# IRIS_Arduino_Shield_2.net
KiCad netlist of a schematic drawn in EAGLE
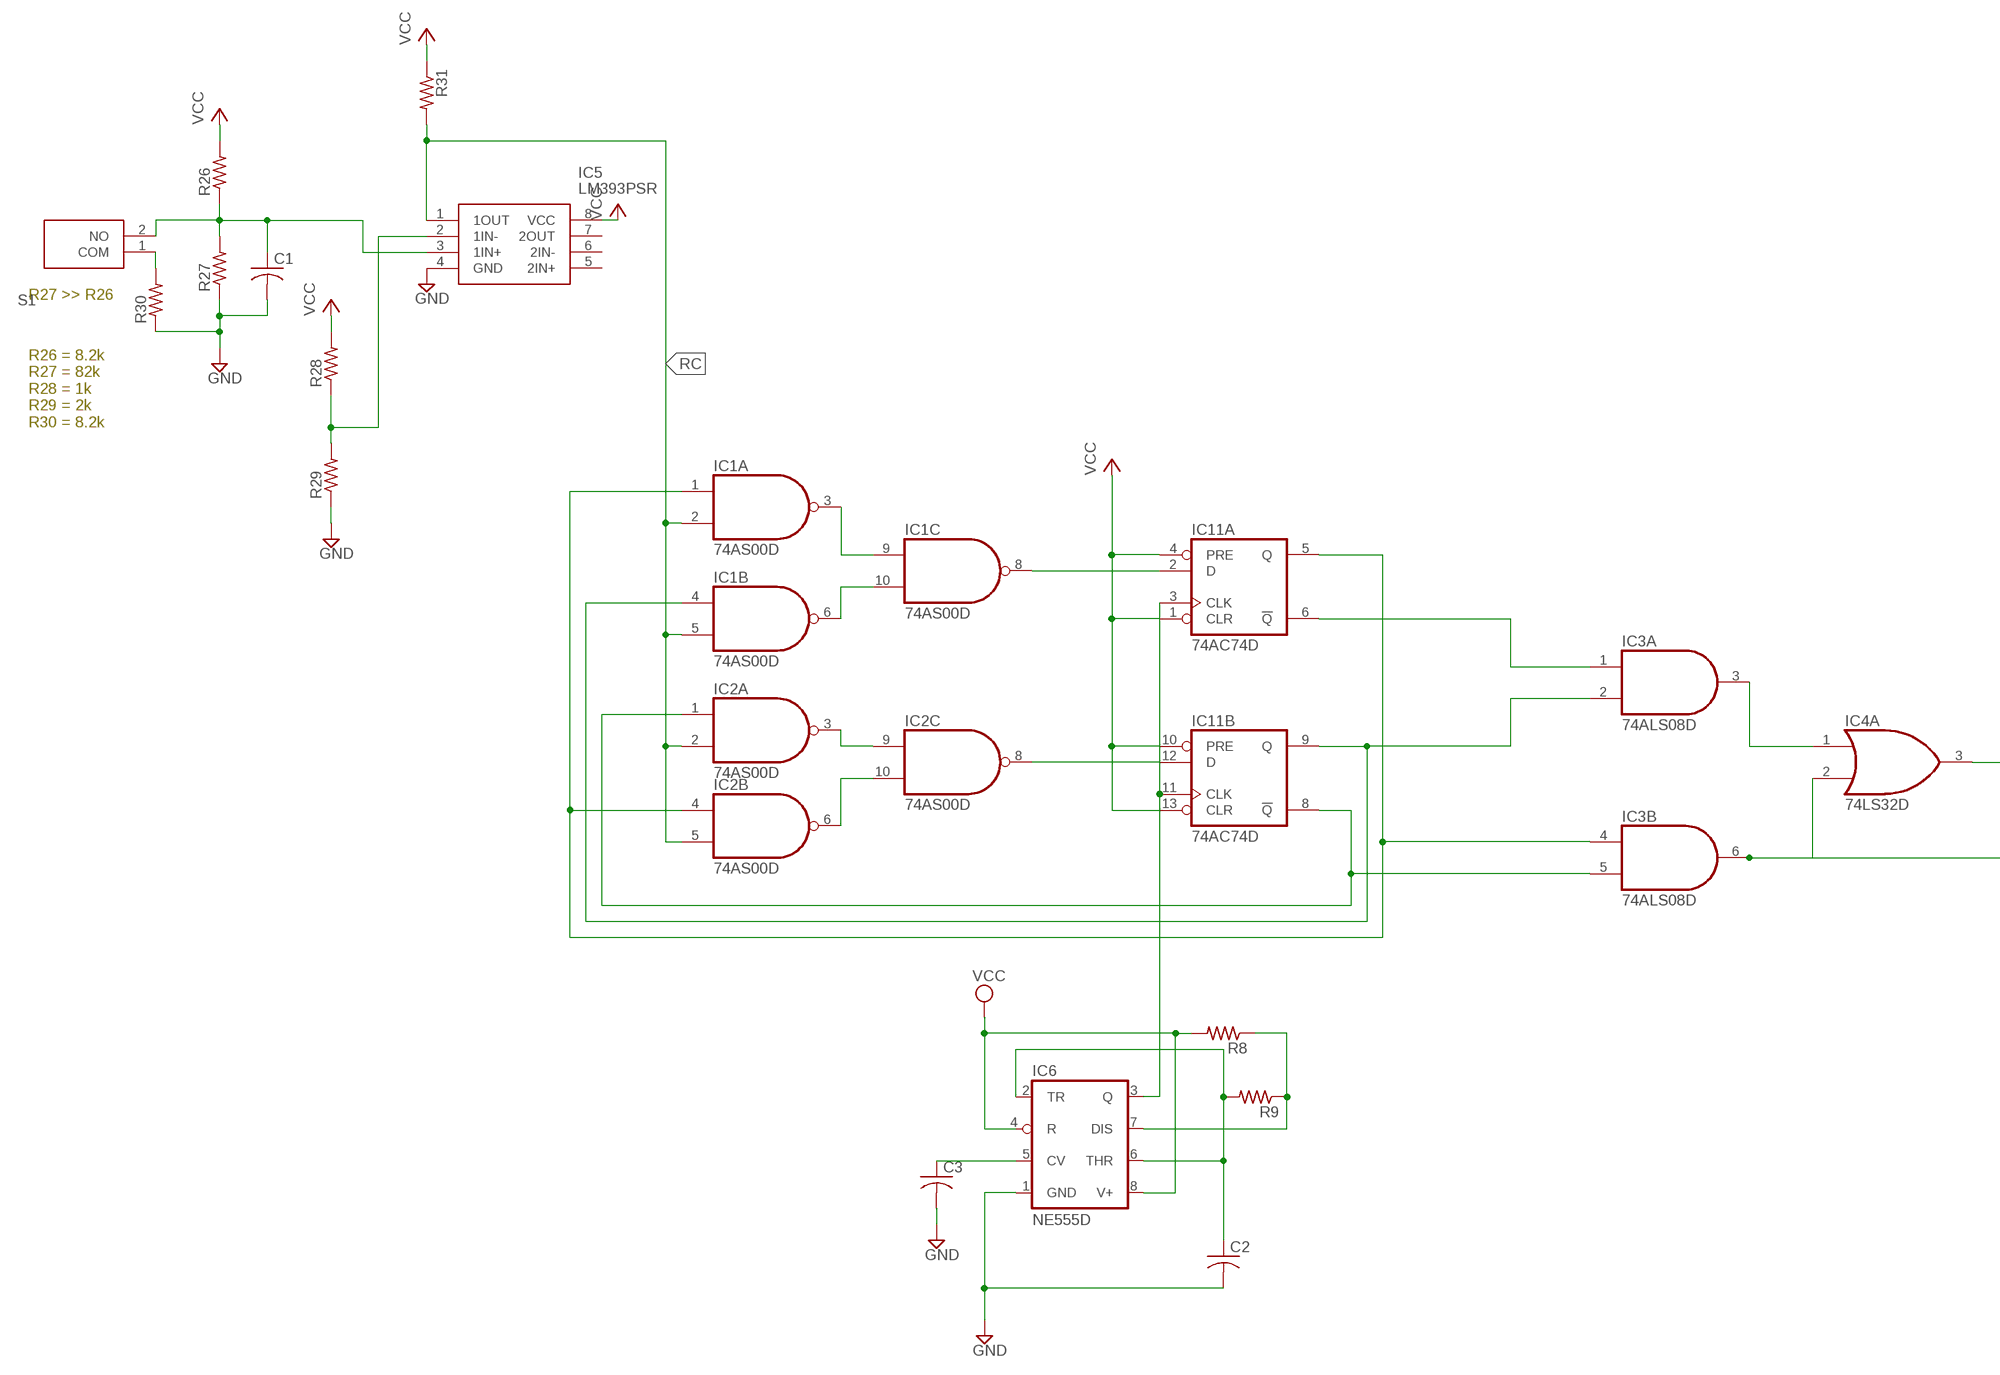
[diagram p0: schematic, sheet 1, part 1 of 2]
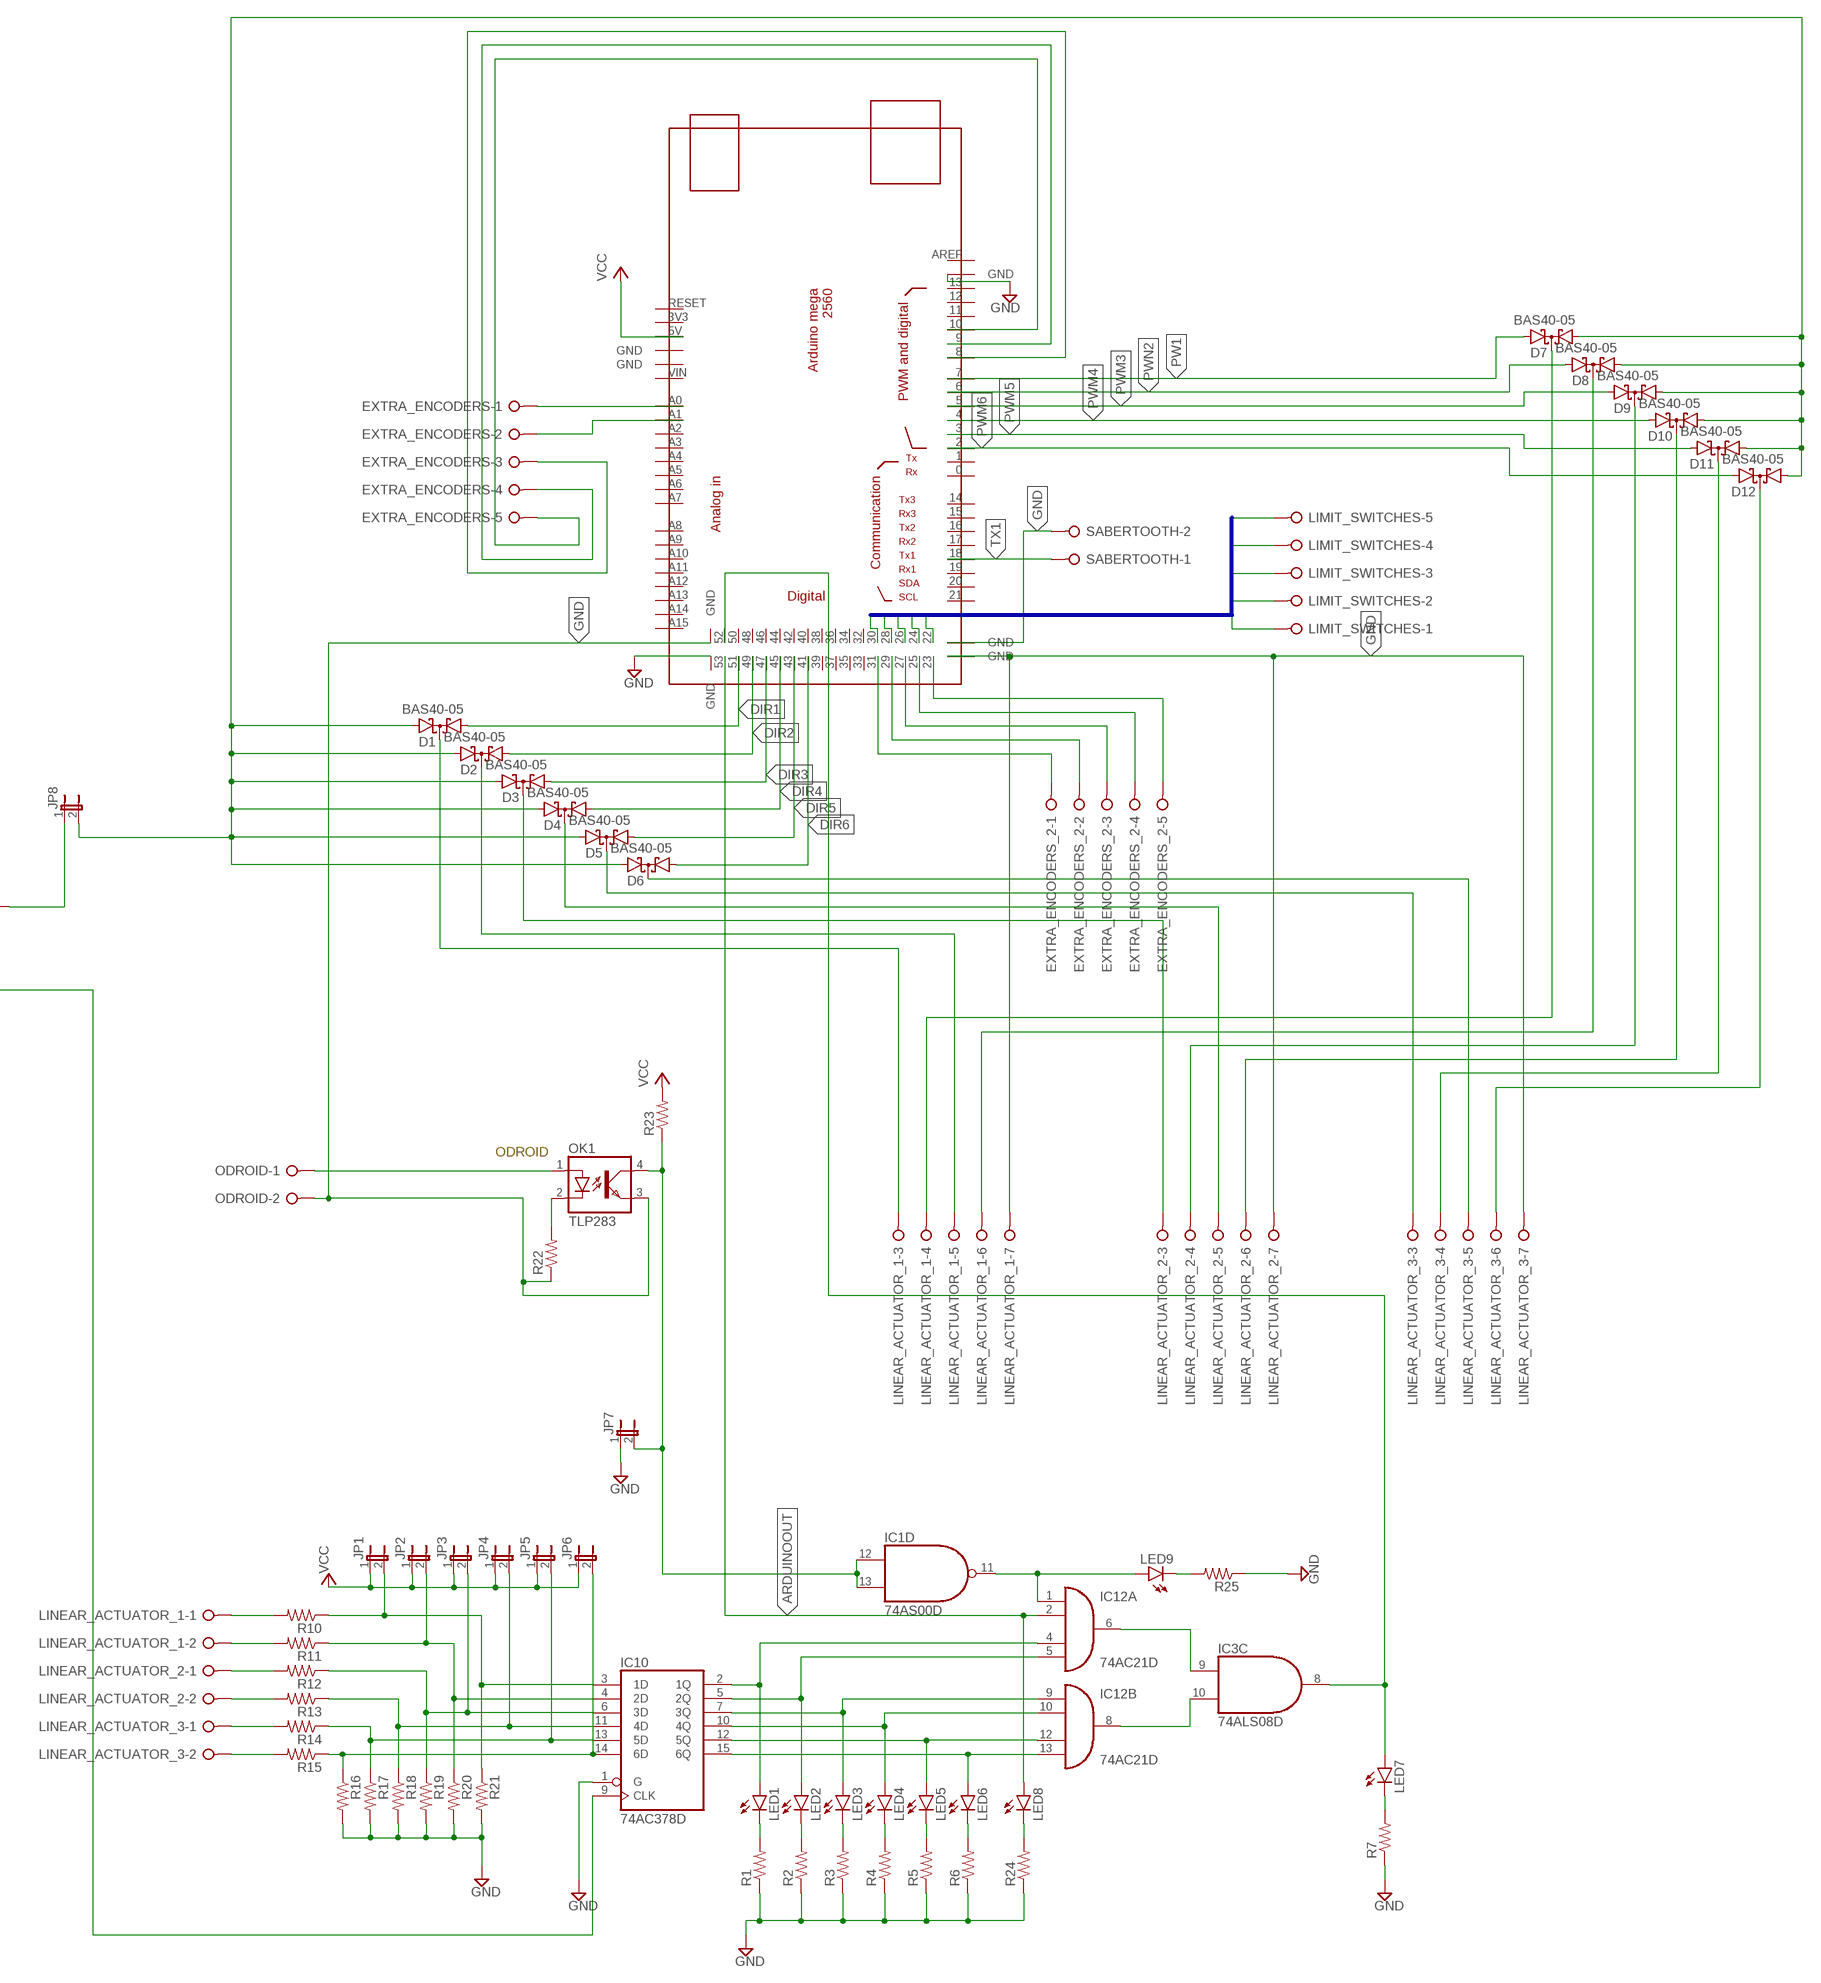
[diagram p1: schematic, sheet 1, part 2 of 2]

(export (version "E")
  (design (tool "Eeschema 10.0.6"))
  (components
    (comp (ref "C1")
      (value "C-USC0805")
      (footprint "eagle-import:C0805")
      (libsource (lib "eagle-import") (part "C-USC0805"))
    )
    (comp (ref "C2")
      (value "C-USC0805")
      (footprint "eagle-import:C0805")
      (libsource (lib "eagle-import") (part "C-USC0805"))
    )
    (comp (ref "C3")
      (value "C-USC0805")
      (footprint "eagle-import:C0805")
      (libsource (lib "eagle-import") (part "C-USC0805"))
    )
    (comp (ref "D1")
      (value "BAS40-05")
      (footprint "eagle-import:SOT23")
      (libsource (lib "eagle-import") (part "BAS40-05"))
    )
    (comp (ref "D2")
      (value "BAS40-05")
      (footprint "eagle-import:SOT23")
      (libsource (lib "eagle-import") (part "BAS40-05"))
    )
    (comp (ref "D3")
      (value "BAS40-05")
      (footprint "eagle-import:SOT23")
      (libsource (lib "eagle-import") (part "BAS40-05"))
    )
    (comp (ref "D4")
      (value "BAS40-05")
      (footprint "eagle-import:SOT23")
      (libsource (lib "eagle-import") (part "BAS40-05"))
    )
    (comp (ref "D5")
      (value "BAS40-05")
      (footprint "eagle-import:SOT23")
      (libsource (lib "eagle-import") (part "BAS40-05"))
    )
    (comp (ref "D6")
      (value "BAS40-05")
      (footprint "eagle-import:SOT23")
      (libsource (lib "eagle-import") (part "BAS40-05"))
    )
    (comp (ref "D7")
      (value "BAS40-05")
      (footprint "eagle-import:SOT23")
      (libsource (lib "eagle-import") (part "BAS40-05"))
    )
    (comp (ref "D8")
      (value "BAS40-05")
      (footprint "eagle-import:SOT23")
      (libsource (lib "eagle-import") (part "BAS40-05"))
    )
    (comp (ref "D9")
      (value "BAS40-05")
      (footprint "eagle-import:SOT23")
      (libsource (lib "eagle-import") (part "BAS40-05"))
    )
    (comp (ref "D10")
      (value "BAS40-05")
      (footprint "eagle-import:SOT23")
      (libsource (lib "eagle-import") (part "BAS40-05"))
    )
    (comp (ref "D11")
      (value "BAS40-05")
      (footprint "eagle-import:SOT23")
      (libsource (lib "eagle-import") (part "BAS40-05"))
    )
    (comp (ref "D12")
      (value "BAS40-05")
      (footprint "eagle-import:SOT23")
      (libsource (lib "eagle-import") (part "BAS40-05"))
    )
    (comp (ref "EXTRA_ENCODERS")
      (value "W237-05P")
      (footprint "eagle-import:W237-5P")
      (libsource (lib "eagle-import") (part "W237-05P"))
    )
    (comp (ref "EXTRA_ENCODERS_2")
      (value "W237-05P")
      (footprint "eagle-import:W237-5P")
      (libsource (lib "eagle-import") (part "W237-05P"))
    )
    (comp (ref "IC1")
      (value "74AS00D")
      (footprint "eagle-import:SO14")
      (libsource (lib "eagle-import") (part "7400DAS"))
    )
    (comp (ref "IC2")
      (value "74AS00D")
      (footprint "eagle-import:SO14")
      (libsource (lib "eagle-import") (part "7400DAS"))
    )
    (comp (ref "IC3")
      (value "74ALS08D")
      (footprint "eagle-import:SO14")
      (libsource (lib "eagle-import") (part "7408DALS"))
    )
    (comp (ref "IC4")
      (value "74LS32D")
      (footprint "eagle-import:SO14")
      (libsource (lib "eagle-import") (part "7432DLS"))
    )
    (comp (ref "IC5")
      (value "LM393PSR")
      (footprint "eagle-import:SOIC127P780X200-8N")
      (fields (field (name "MOUSER_PART_NUMBER") "595-LM393PSR"))
      (libsource (lib "eagle-import") (part "LM393PSR"))
    )
    (comp (ref "IC6")
      (value "NE555D")
      (footprint "eagle-import:SO08")
      (libsource (lib "eagle-import") (part "555DNE"))
    )
    (comp (ref "IC10")
      (value "74AC378D")
      (footprint "eagle-import:SO16")
      (libsource (lib "eagle-import") (part "74378DAC"))
    )
    (comp (ref "IC11")
      (value "74AC74D")
      (footprint "eagle-import:SO14")
      (libsource (lib "eagle-import") (part "7474DAC"))
    )
    (comp (ref "IC12")
      (value "74AC21D")
      (footprint "eagle-import:SO14")
      (libsource (lib "eagle-import") (part "7421DAC"))
    )
    (comp (ref "JP1")
      (value "JP1E")
      (footprint "eagle-import:JP1")
      (libsource (lib "eagle-import") (part "JP1E"))
    )
    (comp (ref "JP2")
      (value "JP1E")
      (footprint "eagle-import:JP1")
      (libsource (lib "eagle-import") (part "JP1E"))
    )
    (comp (ref "JP3")
      (value "JP1E")
      (footprint "eagle-import:JP1")
      (libsource (lib "eagle-import") (part "JP1E"))
    )
    (comp (ref "JP4")
      (value "JP1E")
      (footprint "eagle-import:JP1")
      (libsource (lib "eagle-import") (part "JP1E"))
    )
    (comp (ref "JP5")
      (value "JP1E")
      (footprint "eagle-import:JP1")
      (libsource (lib "eagle-import") (part "JP1E"))
    )
    (comp (ref "JP6")
      (value "JP1E")
      (footprint "eagle-import:JP1")
      (libsource (lib "eagle-import") (part "JP1E"))
    )
    (comp (ref "JP7")
      (value "JP1E")
      (footprint "eagle-import:JP1")
      (libsource (lib "eagle-import") (part "JP1E"))
    )
    (comp (ref "JP8")
      (value "JP1E")
      (footprint "eagle-import:JP1")
      (libsource (lib "eagle-import") (part "JP1E"))
    )
    (comp (ref "LED1")
      (value "LEDCHIPLED_1206")
      (footprint "eagle-import:CHIPLED_1206")
      (libsource (lib "eagle-import") (part "LEDCHIPLED_1206"))
    )
    (comp (ref "LED2")
      (value "LEDCHIPLED_1206")
      (footprint "eagle-import:CHIPLED_1206")
      (libsource (lib "eagle-import") (part "LEDCHIPLED_1206"))
    )
    (comp (ref "LED3")
      (value "LEDCHIPLED_1206")
      (footprint "eagle-import:CHIPLED_1206")
      (libsource (lib "eagle-import") (part "LEDCHIPLED_1206"))
    )
    (comp (ref "LED4")
      (value "LEDCHIPLED_1206")
      (footprint "eagle-import:CHIPLED_1206")
      (libsource (lib "eagle-import") (part "LEDCHIPLED_1206"))
    )
    (comp (ref "LED5")
      (value "LEDCHIPLED_1206")
      (footprint "eagle-import:CHIPLED_1206")
      (libsource (lib "eagle-import") (part "LEDCHIPLED_1206"))
    )
    (comp (ref "LED6")
      (value "LEDCHIPLED_1206")
      (footprint "eagle-import:CHIPLED_1206")
      (libsource (lib "eagle-import") (part "LEDCHIPLED_1206"))
    )
    (comp (ref "LED7")
      (value "LEDCHIPLED_1206")
      (footprint "eagle-import:CHIPLED_1206")
      (libsource (lib "eagle-import") (part "LEDCHIPLED_1206"))
    )
    (comp (ref "LED8")
      (value "LEDCHIPLED_1206")
      (footprint "eagle-import:CHIPLED_1206")
      (libsource (lib "eagle-import") (part "LEDCHIPLED_1206"))
    )
    (comp (ref "LED9")
      (value "LEDCHIPLED_1206")
      (footprint "eagle-import:CHIPLED_1206")
      (libsource (lib "eagle-import") (part "LEDCHIPLED_1206"))
    )
    (comp (ref "LIMIT_SWITCHES")
      (value "W237-05P")
      (footprint "eagle-import:W237-5P")
      (libsource (lib "eagle-import") (part "W237-05P"))
    )
    (comp (ref "LINEAR_ACTUATOR_1")
      (value "W237-07P")
      (footprint "eagle-import:W237-7P")
      (libsource (lib "eagle-import") (part "W237-07P"))
    )
    (comp (ref "LINEAR_ACTUATOR_2")
      (value "W237-07P")
      (footprint "eagle-import:W237-7P")
      (libsource (lib "eagle-import") (part "W237-07P"))
    )
    (comp (ref "LINEAR_ACTUATOR_3")
      (value "W237-07P")
      (footprint "eagle-import:W237-7P")
      (libsource (lib "eagle-import") (part "W237-07P"))
    )
    (comp (ref "ODROID")
      (value "W237-02P")
      (footprint "eagle-import:W237-132")
      (libsource (lib "eagle-import") (part "W237-02P"))
    )
    (comp (ref "OK1")
      (value "TLP283")
      (footprint "eagle-import:MINI-FLAT-4")
      (libsource (lib "eagle-import") (part "TLP283"))
    )
    (comp (ref "R1")
      (value "R-US_R0805")
      (footprint "eagle-import:R0805")
      (libsource (lib "eagle-import") (part "R-US_R0805"))
    )
    (comp (ref "R2")
      (value "R-US_R0805")
      (footprint "eagle-import:R0805")
      (libsource (lib "eagle-import") (part "R-US_R0805"))
    )
    (comp (ref "R3")
      (value "R-US_R0805")
      (footprint "eagle-import:R0805")
      (libsource (lib "eagle-import") (part "R-US_R0805"))
    )
    (comp (ref "R4")
      (value "R-US_R0805")
      (footprint "eagle-import:R0805")
      (libsource (lib "eagle-import") (part "R-US_R0805"))
    )
    (comp (ref "R5")
      (value "R-US_R0805")
      (footprint "eagle-import:R0805")
      (libsource (lib "eagle-import") (part "R-US_R0805"))
    )
    (comp (ref "R6")
      (value "R-US_R0805")
      (footprint "eagle-import:R0805")
      (libsource (lib "eagle-import") (part "R-US_R0805"))
    )
    (comp (ref "R7")
      (value "R-US_R0805")
      (footprint "eagle-import:R0805")
      (libsource (lib "eagle-import") (part "R-US_R0805"))
    )
    (comp (ref "R8")
      (value "R-US_R0805")
      (footprint "eagle-import:R0805")
      (libsource (lib "eagle-import") (part "R-US_R0805"))
    )
    (comp (ref "R9")
      (value "R-US_R0805")
      (footprint "eagle-import:R0805")
      (libsource (lib "eagle-import") (part "R-US_R0805"))
    )
    (comp (ref "R10")
      (value "R-US_R0805")
      (footprint "eagle-import:R0805")
      (libsource (lib "eagle-import") (part "R-US_R0805"))
    )
    (comp (ref "R11")
      (value "R-US_R0805")
      (footprint "eagle-import:R0805")
      (libsource (lib "eagle-import") (part "R-US_R0805"))
    )
    (comp (ref "R12")
      (value "R-US_R0805")
      (footprint "eagle-import:R0805")
      (libsource (lib "eagle-import") (part "R-US_R0805"))
    )
    (comp (ref "R13")
      (value "R-US_R0805")
      (footprint "eagle-import:R0805")
      (libsource (lib "eagle-import") (part "R-US_R0805"))
    )
    (comp (ref "R14")
      (value "R-US_R0805")
      (footprint "eagle-import:R0805")
      (libsource (lib "eagle-import") (part "R-US_R0805"))
    )
    (comp (ref "R15")
      (value "R-US_R0805")
      (footprint "eagle-import:R0805")
      (libsource (lib "eagle-import") (part "R-US_R0805"))
    )
    (comp (ref "R16")
      (value "R-US_R0805")
      (footprint "eagle-import:R0805")
      (libsource (lib "eagle-import") (part "R-US_R0805"))
    )
    (comp (ref "R17")
      (value "R-US_R0805")
      (footprint "eagle-import:R0805")
      (libsource (lib "eagle-import") (part "R-US_R0805"))
    )
    (comp (ref "R18")
      (value "R-US_R0805")
      (footprint "eagle-import:R0805")
      (libsource (lib "eagle-import") (part "R-US_R0805"))
    )
    (comp (ref "R19")
      (value "R-US_R0805")
      (footprint "eagle-import:R0805")
      (libsource (lib "eagle-import") (part "R-US_R0805"))
    )
    (comp (ref "R20")
      (value "R-US_R0805")
      (footprint "eagle-import:R0805")
      (libsource (lib "eagle-import") (part "R-US_R0805"))
    )
    (comp (ref "R21")
      (value "R-US_R0805")
      (footprint "eagle-import:R0805")
      (libsource (lib "eagle-import") (part "R-US_R0805"))
    )
    (comp (ref "R22")
      (value "R-US_R0805")
      (footprint "eagle-import:R0805")
      (libsource (lib "eagle-import") (part "R-US_R0805"))
    )
    (comp (ref "R23")
      (value "R-US_R0805")
      (footprint "eagle-import:R0805")
      (libsource (lib "eagle-import") (part "R-US_R0805"))
    )
    (comp (ref "R24")
      (value "R-US_R0805")
      (footprint "eagle-import:R0805")
      (libsource (lib "eagle-import") (part "R-US_R0805"))
    )
    (comp (ref "R25")
      (value "R-US_R0805")
      (footprint "eagle-import:R0805")
      (libsource (lib "eagle-import") (part "R-US_R0805"))
    )
    (comp (ref "R26")
      (value "R-US_R0805")
      (footprint "eagle-import:R0805")
      (libsource (lib "eagle-import") (part "R-US_R0805"))
    )
    (comp (ref "R27")
      (value "R-US_R0805")
      (footprint "eagle-import:R0805")
      (libsource (lib "eagle-import") (part "R-US_R0805"))
    )
    (comp (ref "R28")
      (value "R-US_R0805")
      (footprint "eagle-import:R0805")
      (libsource (lib "eagle-import") (part "R-US_R0805"))
    )
    (comp (ref "R29")
      (value "R-US_R0805")
      (footprint "eagle-import:R0805")
      (libsource (lib "eagle-import") (part "R-US_R0805"))
    )
    (comp (ref "R30")
      (value "R-US_R0805")
      (footprint "eagle-import:R0805")
      (libsource (lib "eagle-import") (part "R-US_R0805"))
    )
    (comp (ref "R31")
      (value "R-US_R0805")
      (footprint "eagle-import:R0805")
      (libsource (lib "eagle-import") (part "R-US_R0805"))
    )
    (comp (ref "S1")
      (value "PTS636_SL43_SMTR_LFS")
      (footprint "eagle-import:PTS636SL43SMTRLFS")
      (fields
        (field (name "MANUFACTURER_PART_NUMBER") "PTS636 SL43 SMTR LFS")
        (field (name "MOUSER_PART_NUMBER") "611-PTS636SL43SMTRLF")
      )
      (libsource (lib "eagle-import") (part "PTS636_SL43_SMTR_LFS"))
    )
    (comp (ref "SABERTOOTH")
      (value "W237-02P")
      (footprint "eagle-import:W237-132")
      (libsource (lib "eagle-import") (part "W237-02P"))
    )
    (comp (ref "U$1")
      (value "MEGA_DEVICE")
      (footprint "eagle-import:MEGAOUTLINE")
      (libsource (lib "eagle-import") (part "MEGA_DEVICE"))
    )
  )
  (nets
    (net (code "1") (name "/N$77") (class "Default")
      (node (ref "LIMIT_SWITCHES") (pin "1") (pinfunction "KL_1") (pintype "passive"))
      (node (ref "U$1") (pin "30") (pinfunction "30_30") (pintype "bidirectional"))
    )
    (net (code "2") (name "/N$78") (class "Default")
      (node (ref "LIMIT_SWITCHES") (pin "2") (pinfunction "KL_2") (pintype "passive"))
      (node (ref "U$1") (pin "28") (pinfunction "28_28") (pintype "bidirectional"))
    )
    (net (code "3") (name "/N$79") (class "Default")
      (node (ref "LIMIT_SWITCHES") (pin "3") (pinfunction "KL_3") (pintype "passive"))
      (node (ref "U$1") (pin "26") (pinfunction "26_26") (pintype "bidirectional"))
    )
    (net (code "4") (name "/N$80") (class "Default")
      (node (ref "LIMIT_SWITCHES") (pin "4") (pinfunction "KL_4") (pintype "passive"))
      (node (ref "U$1") (pin "24") (pinfunction "24_24") (pintype "bidirectional"))
    )
    (net (code "5") (name "/N$81") (class "Default")
      (node (ref "LIMIT_SWITCHES") (pin "5") (pinfunction "KL_5") (pintype "passive"))
      (node (ref "U$1") (pin "22") (pinfunction "22_22") (pintype "bidirectional"))
    )
    (net (code "6") (name "ARDUINOOUT") (class "Default")
      (node (ref "IC12") (pin "2") (pinfunction "I1_2") (pintype "input"))
      (node (ref "LED8") (pin "A") (pinfunction "A_A") (pintype "passive"))
      (node (ref "U$1") (pin "53") (pinfunction "53_53") (pintype "bidirectional"))
    )
    (net (code "7") (name "DIR1") (class "Default")
      (node (ref "D1") (pin "1") (pinfunction "A1_1") (pintype "passive"))
      (node (ref "U$1") (pin "51") (pinfunction "51_51") (pintype "bidirectional"))
    )
    (net (code "8") (name "DIR2") (class "Default")
      (node (ref "D2") (pin "1") (pinfunction "A1_1") (pintype "passive"))
      (node (ref "U$1") (pin "49") (pinfunction "49_49") (pintype "bidirectional"))
    )
    (net (code "9") (name "DIR3") (class "Default")
      (node (ref "D3") (pin "1") (pinfunction "A1_1") (pintype "passive"))
      (node (ref "U$1") (pin "47") (pinfunction "47_47") (pintype "bidirectional"))
    )
    (net (code "10") (name "DIR4") (class "Default")
      (node (ref "D4") (pin "1") (pinfunction "A1_1") (pintype "passive"))
      (node (ref "U$1") (pin "45") (pinfunction "45_45") (pintype "bidirectional"))
    )
    (net (code "11") (name "DIR5") (class "Default")
      (node (ref "D5") (pin "1") (pinfunction "A1_1") (pintype "passive"))
      (node (ref "U$1") (pin "43") (pinfunction "43_43") (pintype "bidirectional"))
    )
    (net (code "12") (name "DIR6") (class "Default")
      (node (ref "D6") (pin "1") (pinfunction "A1_1") (pintype "passive"))
      (node (ref "U$1") (pin "41") (pinfunction "41_41") (pintype "bidirectional"))
    )
    (net (code "13") (name "GND") (class "Default")
      (node (ref "C1") (pin "2") (pinfunction "2_2") (pintype "passive"))
      (node (ref "C2") (pin "2") (pinfunction "2_2") (pintype "passive"))
      (node (ref "C3") (pin "2") (pinfunction "2_2") (pintype "passive"))
      (node (ref "IC10") (pin "1") (pinfunction "G_1") (pintype "input"))
      (node (ref "IC5") (pin "4") (pinfunction "GND_4") (pintype "bidirectional"))
      (node (ref "IC6") (pin "1") (pinfunction "GND_1") (pintype "power_in"))
      (node (ref "JP7") (pin "1") (pinfunction "1_1") (pintype "passive"))
      (node (ref "LINEAR_ACTUATOR_1") (pin "7") (pinfunction "KL_7") (pintype "passive"))
      (node (ref "LINEAR_ACTUATOR_2") (pin "7") (pinfunction "KL_7") (pintype "passive"))
      (node (ref "LINEAR_ACTUATOR_3") (pin "7") (pinfunction "KL_7") (pintype "passive"))
      (node (ref "ODROID") (pin "2") (pinfunction "KL_2") (pintype "passive"))
      (node (ref "OK1") (pin "3") (pinfunction "EMIT_3") (pintype "passive"))
      (node (ref "R1") (pin "1") (pinfunction "1_1") (pintype "passive"))
      (node (ref "R16") (pin "2") (pinfunction "2_2") (pintype "passive"))
      (node (ref "R17") (pin "2") (pinfunction "2_2") (pintype "passive"))
      (node (ref "R18") (pin "2") (pinfunction "2_2") (pintype "passive"))
      (node (ref "R19") (pin "2") (pinfunction "2_2") (pintype "passive"))
      (node (ref "R2") (pin "1") (pinfunction "1_1") (pintype "passive"))
      (node (ref "R20") (pin "2") (pinfunction "2_2") (pintype "passive"))
      (node (ref "R21") (pin "2") (pinfunction "2_2") (pintype "passive"))
      (node (ref "R22") (pin "1") (pinfunction "1_1") (pintype "passive"))
      (node (ref "R24") (pin "1") (pinfunction "1_1") (pintype "passive"))
      (node (ref "R25") (pin "1") (pinfunction "1_1") (pintype "passive"))
      (node (ref "R27") (pin "1") (pinfunction "1_1") (pintype "passive"))
      (node (ref "R29") (pin "1") (pinfunction "1_1") (pintype "passive"))
      (node (ref "R3") (pin "1") (pinfunction "1_1") (pintype "passive"))
      (node (ref "R30") (pin "1") (pinfunction "1_1") (pintype "passive"))
      (node (ref "R4") (pin "1") (pinfunction "1_1") (pintype "passive"))
      (node (ref "R5") (pin "1") (pinfunction "1_1") (pintype "passive"))
      (node (ref "R6") (pin "1") (pinfunction "1_1") (pintype "passive"))
      (node (ref "R7") (pin "1") (pinfunction "1_1") (pintype "passive"))
      (node (ref "SABERTOOTH") (pin "2") (pinfunction "KL_2") (pintype "passive"))
      (node (ref "U$1") (pin "GND@1") (pinfunction "GND_GND@1") (pintype "bidirectional"))
      (node (ref "U$1") (pin "GND@4") (pinfunction "GND_GND@4") (pintype "bidirectional"))
      (node (ref "U$1") (pin "GND@5") (pinfunction "GND_GND@5") (pintype "bidirectional"))
      (node (ref "U$1") (pin "GND@6") (pinfunction "GND_GND@6") (pintype "bidirectional"))
      (node (ref "U$1") (pin "GND@7") (pinfunction "GND_GND@7") (pintype "bidirectional"))
    )
    (net (code "14") (name "Net-(D1-A2)") (class "Default")
      (node (ref "D1") (pin "2") (pinfunction "A2_2") (pintype "passive"))
      (node (ref "D10") (pin "1") (pinfunction "A1_1") (pintype "passive"))
      (node (ref "D11") (pin "1") (pinfunction "A1_1") (pintype "passive"))
      (node (ref "D12") (pin "1") (pinfunction "A1_1") (pintype "passive"))
      (node (ref "D2") (pin "2") (pinfunction "A2_2") (pintype "passive"))
      (node (ref "D3") (pin "2") (pinfunction "A2_2") (pintype "passive"))
      (node (ref "D4") (pin "2") (pinfunction "A2_2") (pintype "passive"))
      (node (ref "D5") (pin "2") (pinfunction "A2_2") (pintype "passive"))
      (node (ref "D6") (pin "2") (pinfunction "A2_2") (pintype "passive"))
      (node (ref "D7") (pin "1") (pinfunction "A1_1") (pintype "passive"))
      (node (ref "D8") (pin "1") (pinfunction "A1_1") (pintype "passive"))
      (node (ref "D9") (pin "1") (pinfunction "A1_1") (pintype "passive"))
      (node (ref "JP8") (pin "2") (pinfunction "2_2") (pintype "passive"))
    )
    (net (code "15") (name "Net-(D1-C)") (class "Default")
      (node (ref "D1") (pin "3") (pinfunction "C_3") (pintype "passive"))
      (node (ref "LINEAR_ACTUATOR_1") (pin "3") (pinfunction "KL_3") (pintype "passive"))
    )
    (net (code "16") (name "Net-(D2-C)") (class "Default")
      (node (ref "D2") (pin "3") (pinfunction "C_3") (pintype "passive"))
      (node (ref "LINEAR_ACTUATOR_1") (pin "5") (pinfunction "KL_5") (pintype "passive"))
    )
    (net (code "17") (name "Net-(D3-C)") (class "Default")
      (node (ref "D3") (pin "3") (pinfunction "C_3") (pintype "passive"))
      (node (ref "LINEAR_ACTUATOR_2") (pin "3") (pinfunction "KL_3") (pintype "passive"))
    )
    (net (code "18") (name "Net-(D4-C)") (class "Default")
      (node (ref "D4") (pin "3") (pinfunction "C_3") (pintype "passive"))
      (node (ref "LINEAR_ACTUATOR_2") (pin "5") (pinfunction "KL_5") (pintype "passive"))
    )
    (net (code "19") (name "Net-(D5-C)") (class "Default")
      (node (ref "D5") (pin "3") (pinfunction "C_3") (pintype "passive"))
      (node (ref "LINEAR_ACTUATOR_3") (pin "3") (pinfunction "KL_3") (pintype "passive"))
    )
    (net (code "20") (name "Net-(D6-C)") (class "Default")
      (node (ref "D6") (pin "3") (pinfunction "C_3") (pintype "passive"))
      (node (ref "LINEAR_ACTUATOR_3") (pin "5") (pinfunction "KL_5") (pintype "passive"))
    )
    (net (code "21") (name "Net-(D7-C)") (class "Default")
      (node (ref "D7") (pin "3") (pinfunction "C_3") (pintype "passive"))
      (node (ref "LINEAR_ACTUATOR_1") (pin "4") (pinfunction "KL_4") (pintype "passive"))
    )
    (net (code "22") (name "Net-(D8-C)") (class "Default")
      (node (ref "D8") (pin "3") (pinfunction "C_3") (pintype "passive"))
      (node (ref "LINEAR_ACTUATOR_1") (pin "6") (pinfunction "KL_6") (pintype "passive"))
    )
    (net (code "23") (name "Net-(D9-C)") (class "Default")
      (node (ref "D9") (pin "3") (pinfunction "C_3") (pintype "passive"))
      (node (ref "LINEAR_ACTUATOR_2") (pin "4") (pinfunction "KL_4") (pintype "passive"))
    )
    (net (code "24") (name "Net-(D10-C)") (class "Default")
      (node (ref "D10") (pin "3") (pinfunction "C_3") (pintype "passive"))
      (node (ref "LINEAR_ACTUATOR_2") (pin "6") (pinfunction "KL_6") (pintype "passive"))
    )
    (net (code "25") (name "Net-(D11-C)") (class "Default")
      (node (ref "D11") (pin "3") (pinfunction "C_3") (pintype "passive"))
      (node (ref "LINEAR_ACTUATOR_3") (pin "4") (pinfunction "KL_4") (pintype "passive"))
    )
    (net (code "26") (name "Net-(D12-C)") (class "Default")
      (node (ref "D12") (pin "3") (pinfunction "C_3") (pintype "passive"))
      (node (ref "LINEAR_ACTUATOR_3") (pin "6") (pinfunction "KL_6") (pintype "passive"))
    )
    (net (code "27") (name "Net-(EXTRA_ENCODERSA-KL)") (class "Default")
      (node (ref "EXTRA_ENCODERS") (pin "1") (pinfunction "KL_1") (pintype "passive"))
      (node (ref "U$1") (pin "A0") (pinfunction "A0_A0") (pintype "bidirectional"))
    )
    (net (code "28") (name "Net-(EXTRA_ENCODERSB-KL)") (class "Default")
      (node (ref "EXTRA_ENCODERS") (pin "2") (pinfunction "KL_2") (pintype "passive"))
      (node (ref "U$1") (pin "A1") (pinfunction "A1_A1") (pintype "bidirectional"))
    )
    (net (code "29") (name "Net-(EXTRA_ENCODERSC-KL)") (class "Default")
      (node (ref "EXTRA_ENCODERS") (pin "3") (pinfunction "KL_3") (pintype "passive"))
      (node (ref "U$1") (pin "8") (pinfunction "8_8") (pintype "bidirectional"))
    )
    (net (code "30") (name "Net-(EXTRA_ENCODERSD-KL)") (class "Default")
      (node (ref "EXTRA_ENCODERS") (pin "4") (pinfunction "KL_4") (pintype "passive"))
      (node (ref "U$1") (pin "9") (pinfunction "9_9") (pintype "bidirectional"))
    )
    (net (code "31") (name "Net-(EXTRA_ENCODERSE-KL)") (class "Default")
      (node (ref "EXTRA_ENCODERS") (pin "5") (pinfunction "KL_5") (pintype "passive"))
      (node (ref "U$1") (pin "10") (pinfunction "10_10") (pintype "bidirectional"))
    )
    (net (code "32") (name "Net-(EXTRA_ENCODERS_2A-KL)") (class "Default")
      (node (ref "EXTRA_ENCODERS_2") (pin "1") (pinfunction "KL_1") (pintype "passive"))
      (node (ref "U$1") (pin "31") (pinfunction "31_31") (pintype "bidirectional"))
    )
    (net (code "33") (name "Net-(EXTRA_ENCODERS_2B-KL)") (class "Default")
      (node (ref "EXTRA_ENCODERS_2") (pin "2") (pinfunction "KL_2") (pintype "passive"))
      (node (ref "U$1") (pin "29") (pinfunction "29_29") (pintype "bidirectional"))
    )
    (net (code "34") (name "Net-(EXTRA_ENCODERS_2C-KL)") (class "Default")
      (node (ref "EXTRA_ENCODERS_2") (pin "3") (pinfunction "KL_3") (pintype "passive"))
      (node (ref "U$1") (pin "27") (pinfunction "27_27") (pintype "bidirectional"))
    )
    (net (code "35") (name "Net-(EXTRA_ENCODERS_2D-KL)") (class "Default")
      (node (ref "EXTRA_ENCODERS_2") (pin "4") (pinfunction "KL_4") (pintype "passive"))
      (node (ref "U$1") (pin "25") (pinfunction "25_25") (pintype "bidirectional"))
    )
    (net (code "36") (name "Net-(EXTRA_ENCODERS_2E-KL)") (class "Default")
      (node (ref "EXTRA_ENCODERS_2") (pin "5") (pinfunction "KL_5") (pintype "passive"))
      (node (ref "U$1") (pin "23") (pinfunction "23_23") (pintype "bidirectional"))
    )
    (net (code "37") (name "Net-(IC1A-O)") (class "Default")
      (node (ref "IC1") (pin "3") (pinfunction "O_3") (pintype "output"))
      (node (ref "IC1") (pin "9") (pinfunction "I0_9") (pintype "input"))
    )
    (net (code "38") (name "Net-(IC1B-O)") (class "Default")
      (node (ref "IC1") (pin "10") (pinfunction "I1_10") (pintype "input"))
      (node (ref "IC1") (pin "6") (pinfunction "O_6") (pintype "output"))
    )
    (net (code "39") (name "Net-(IC1D-I0)") (class "Default")
      (node (ref "IC1") (pin "12") (pinfunction "I0_12") (pintype "input"))
      (node (ref "IC1") (pin "13") (pinfunction "I1_13") (pintype "input"))
      (node (ref "JP7") (pin "2") (pinfunction "2_2") (pintype "passive"))
      (node (ref "OK1") (pin "4") (pinfunction "COL_4") (pintype "passive"))
      (node (ref "R23") (pin "1") (pinfunction "1_1") (pintype "passive"))
    )
    (net (code "40") (name "Net-(IC2A-O)") (class "Default")
      (node (ref "IC2") (pin "3") (pinfunction "O_3") (pintype "output"))
      (node (ref "IC2") (pin "9") (pinfunction "I0_9") (pintype "input"))
    )
    (net (code "41") (name "Net-(IC2B-O)") (class "Default")
      (node (ref "IC2") (pin "10") (pinfunction "I1_10") (pintype "input"))
      (node (ref "IC2") (pin "6") (pinfunction "O_6") (pintype "output"))
    )
    (net (code "42") (name "Net-(IC3A-O)") (class "Default")
      (node (ref "IC3") (pin "3") (pinfunction "O_3") (pintype "output"))
      (node (ref "IC4") (pin "1") (pinfunction "I0_1") (pintype "input"))
    )
    (net (code "43") (name "Net-(IC3C-O)") (class "Default")
      (node (ref "IC3") (pin "8") (pinfunction "O_8") (pintype "output"))
      (node (ref "LED7") (pin "A") (pinfunction "A_A") (pintype "passive"))
      (node (ref "U$1") (pin "52") (pinfunction "52_52") (pintype "bidirectional"))
    )
    (net (code "44") (name "Net-(IC4A-O)") (class "Default")
      (node (ref "IC4") (pin "3") (pinfunction "O_3") (pintype "output"))
      (node (ref "JP8") (pin "1") (pinfunction "1_1") (pintype "passive"))
    )
    (net (code "45") (name "Net-(IC5-1IN+)") (class "Default")
      (node (ref "C1") (pin "1") (pinfunction "1_1") (pintype "passive"))
      (node (ref "IC5") (pin "3") (pinfunction "1IN+_3") (pintype "bidirectional"))
      (node (ref "R26") (pin "1") (pinfunction "1_1") (pintype "passive"))
      (node (ref "R27") (pin "2") (pinfunction "2_2") (pintype "passive"))
      (node (ref "S1") (pin "2") (pinfunction "NO_2") (pintype "bidirectional"))
    )
    (net (code "46") (name "Net-(IC5-1IN-)") (class "Default")
      (node (ref "IC5") (pin "2") (pinfunction "1IN-_2") (pintype "bidirectional"))
      (node (ref "R28") (pin "1") (pinfunction "1_1") (pintype "passive"))
      (node (ref "R29") (pin "2") (pinfunction "2_2") (pintype "passive"))
    )
    (net (code "47") (name "Net-(IC6-CV)") (class "Default")
      (node (ref "C3") (pin "1") (pinfunction "1_1") (pintype "passive"))
      (node (ref "IC6") (pin "5") (pinfunction "CV_5") (pintype "input"))
    )
    (net (code "48") (name "Net-(IC6-DIS)") (class "Default")
      (node (ref "IC6") (pin "7") (pinfunction "DIS_7") (pintype "input"))
      (node (ref "R8") (pin "1") (pinfunction "1_1") (pintype "passive"))
      (node (ref "R9") (pin "1") (pinfunction "1_1") (pintype "passive"))
    )
    (net (code "49") (name "Net-(IC6-THR)") (class "Default")
      (node (ref "C2") (pin "1") (pinfunction "1_1") (pintype "passive"))
      (node (ref "IC6") (pin "2") (pinfunction "TR_2") (pintype "input"))
      (node (ref "IC6") (pin "6") (pinfunction "THR_6") (pintype "input"))
      (node (ref "R9") (pin "2") (pinfunction "2_2") (pintype "passive"))
    )
    (net (code "50") (name "Net-(IC10A-1D)") (class "Default")
      (node (ref "IC10") (pin "3") (pinfunction "1D_3") (pintype "input"))
      (node (ref "JP1") (pin "2") (pinfunction "2_2") (pintype "passive"))
      (node (ref "R10") (pin "1") (pinfunction "1_1") (pintype "passive"))
      (node (ref "R21") (pin "1") (pinfunction "1_1") (pintype "passive"))
    )
    (net (code "51") (name "Net-(IC10A-1Q)") (class "Default")
      (node (ref "IC10") (pin "2") (pinfunction "1Q_2") (pintype "output"))
      (node (ref "IC12") (pin "4") (pinfunction "I2_4") (pintype "input"))
      (node (ref "LED1") (pin "A") (pinfunction "A_A") (pintype "passive"))
    )
    (net (code "52") (name "Net-(IC10A-2D)") (class "Default")
      (node (ref "IC10") (pin "4") (pinfunction "2D_4") (pintype "input"))
      (node (ref "JP2") (pin "2") (pinfunction "2_2") (pintype "passive"))
      (node (ref "R11") (pin "1") (pinfunction "1_1") (pintype "passive"))
      (node (ref "R20") (pin "1") (pinfunction "1_1") (pintype "passive"))
    )
    (net (code "53") (name "Net-(IC10A-2Q)") (class "Default")
      (node (ref "IC10") (pin "5") (pinfunction "2Q_5") (pintype "output"))
      (node (ref "IC12") (pin "5") (pinfunction "I3_5") (pintype "input"))
      (node (ref "LED2") (pin "A") (pinfunction "A_A") (pintype "passive"))
    )
    (net (code "54") (name "Net-(IC10A-3D)") (class "Default")
      (node (ref "IC10") (pin "6") (pinfunction "3D_6") (pintype "input"))
      (node (ref "JP3") (pin "2") (pinfunction "2_2") (pintype "passive"))
      (node (ref "R12") (pin "1") (pinfunction "1_1") (pintype "passive"))
      (node (ref "R19") (pin "1") (pinfunction "1_1") (pintype "passive"))
    )
    (net (code "55") (name "Net-(IC10A-3Q)") (class "Default")
      (node (ref "IC10") (pin "7") (pinfunction "3Q_7") (pintype "output"))
      (node (ref "IC12") (pin "9") (pinfunction "I0_9") (pintype "input"))
      (node (ref "LED3") (pin "A") (pinfunction "A_A") (pintype "passive"))
    )
    (net (code "56") (name "Net-(IC10A-4D)") (class "Default")
      (node (ref "IC10") (pin "11") (pinfunction "4D_11") (pintype "input"))
      (node (ref "JP4") (pin "2") (pinfunction "2_2") (pintype "passive"))
      (node (ref "R13") (pin "1") (pinfunction "1_1") (pintype "passive"))
      (node (ref "R18") (pin "1") (pinfunction "1_1") (pintype "passive"))
    )
    (net (code "57") (name "Net-(IC10A-4Q)") (class "Default")
      (node (ref "IC10") (pin "10") (pinfunction "4Q_10") (pintype "output"))
      (node (ref "IC12") (pin "10") (pinfunction "I1_10") (pintype "input"))
      (node (ref "LED4") (pin "A") (pinfunction "A_A") (pintype "passive"))
    )
    (net (code "58") (name "Net-(IC10A-5D)") (class "Default")
      (node (ref "IC10") (pin "13") (pinfunction "5D_13") (pintype "input"))
      (node (ref "JP5") (pin "2") (pinfunction "2_2") (pintype "passive"))
      (node (ref "R14") (pin "1") (pinfunction "1_1") (pintype "passive"))
      (node (ref "R17") (pin "1") (pinfunction "1_1") (pintype "passive"))
    )
    (net (code "59") (name "Net-(IC10A-5Q)") (class "Default")
      (node (ref "IC10") (pin "12") (pinfunction "5Q_12") (pintype "output"))
      (node (ref "IC12") (pin "12") (pinfunction "I2_12") (pintype "input"))
      (node (ref "LED5") (pin "A") (pinfunction "A_A") (pintype "passive"))
    )
    (net (code "60") (name "Net-(IC10A-6D)") (class "Default")
      (node (ref "IC10") (pin "14") (pinfunction "6D_14") (pintype "input"))
      (node (ref "JP6") (pin "2") (pinfunction "2_2") (pintype "passive"))
      (node (ref "R15") (pin "1") (pinfunction "1_1") (pintype "passive"))
      (node (ref "R16") (pin "1") (pinfunction "1_1") (pintype "passive"))
    )
    (net (code "61") (name "Net-(IC10A-6Q)") (class "Default")
      (node (ref "IC10") (pin "15") (pinfunction "6Q_15") (pintype "output"))
      (node (ref "IC12") (pin "13") (pinfunction "I3_13") (pintype "input"))
      (node (ref "LED6") (pin "A") (pinfunction "A_A") (pintype "passive"))
    )
    (net (code "62") (name "Net-(IC10A-CLK)") (class "Default")
      (node (ref "IC10") (pin "9") (pinfunction "CLK_9") (pintype "input"))
      (node (ref "IC3") (pin "6") (pinfunction "O_6") (pintype "output"))
      (node (ref "IC4") (pin "2") (pinfunction "I1_2") (pintype "input"))
    )
    (net (code "63") (name "Net-(IC11A-CLK)") (class "Default")
      (node (ref "IC11") (pin "11") (pinfunction "CLK_11") (pintype "input"))
      (node (ref "IC11") (pin "3") (pinfunction "CLK_3") (pintype "input"))
      (node (ref "IC6") (pin "3") (pinfunction "Q_3") (pintype "output"))
    )
    (net (code "64") (name "Net-(IC11A-D)") (class "Default")
      (node (ref "IC1") (pin "8") (pinfunction "O_8") (pintype "output"))
      (node (ref "IC11") (pin "2") (pinfunction "D_2") (pintype "input"))
    )
    (net (code "65") (name "Net-(IC11A-Q)") (class "Default")
      (node (ref "IC1") (pin "1") (pinfunction "I0_1") (pintype "input"))
      (node (ref "IC11") (pin "5") (pinfunction "Q_5") (pintype "output"))
      (node (ref "IC2") (pin "4") (pinfunction "I0_4") (pintype "input"))
      (node (ref "IC3") (pin "4") (pinfunction "I0_4") (pintype "input"))
    )
    (net (code "66") (name "Net-(IC11A-~{Q})") (class "Default")
      (node (ref "IC11") (pin "6") (pinfunction "~{Q}_6") (pintype "output"))
      (node (ref "IC3") (pin "1") (pinfunction "I0_1") (pintype "input"))
    )
    (net (code "67") (name "Net-(IC11B-D)") (class "Default")
      (node (ref "IC11") (pin "12") (pinfunction "D_12") (pintype "input"))
      (node (ref "IC2") (pin "8") (pinfunction "O_8") (pintype "output"))
    )
    (net (code "68") (name "Net-(IC11B-Q)") (class "Default")
      (node (ref "IC1") (pin "4") (pinfunction "I0_4") (pintype "input"))
      (node (ref "IC11") (pin "9") (pinfunction "Q_9") (pintype "output"))
      (node (ref "IC3") (pin "2") (pinfunction "I1_2") (pintype "input"))
    )
    (net (code "69") (name "Net-(IC11B-~{Q})") (class "Default")
      (node (ref "IC11") (pin "8") (pinfunction "~{Q}_8") (pintype "output"))
      (node (ref "IC2") (pin "1") (pinfunction "I0_1") (pintype "input"))
      (node (ref "IC3") (pin "5") (pinfunction "I1_5") (pintype "input"))
    )
    (net (code "70") (name "Net-(IC12A-I0)") (class "Default")
      (node (ref "IC1") (pin "11") (pinfunction "O_11") (pintype "output"))
      (node (ref "IC12") (pin "1") (pinfunction "I0_1") (pintype "input"))
      (node (ref "LED9") (pin "A") (pinfunction "A_A") (pintype "passive"))
    )
    (net (code "71") (name "Net-(IC12A-O)") (class "Default")
      (node (ref "IC12") (pin "6") (pinfunction "O_6") (pintype "output"))
      (node (ref "IC3") (pin "9") (pinfunction "I0_9") (pintype "input"))
    )
    (net (code "72") (name "Net-(IC12B-O)") (class "Default")
      (node (ref "IC12") (pin "8") (pinfunction "O_8") (pintype "output"))
      (node (ref "IC3") (pin "10") (pinfunction "I1_10") (pintype "input"))
    )
    (net (code "73") (name "Net-(LED1-PadC)") (class "Default")
      (node (ref "LED1") (pin "C") (pinfunction "C_C") (pintype "passive"))
      (node (ref "R1") (pin "2") (pinfunction "2_2") (pintype "passive"))
    )
    (net (code "74") (name "Net-(LED2-PadC)") (class "Default")
      (node (ref "LED2") (pin "C") (pinfunction "C_C") (pintype "passive"))
      (node (ref "R2") (pin "2") (pinfunction "2_2") (pintype "passive"))
    )
    (net (code "75") (name "Net-(LED3-PadC)") (class "Default")
      (node (ref "LED3") (pin "C") (pinfunction "C_C") (pintype "passive"))
      (node (ref "R3") (pin "2") (pinfunction "2_2") (pintype "passive"))
    )
    (net (code "76") (name "Net-(LED4-PadC)") (class "Default")
      (node (ref "LED4") (pin "C") (pinfunction "C_C") (pintype "passive"))
      (node (ref "R4") (pin "2") (pinfunction "2_2") (pintype "passive"))
    )
    (net (code "77") (name "Net-(LED5-PadC)") (class "Default")
      (node (ref "LED5") (pin "C") (pinfunction "C_C") (pintype "passive"))
      (node (ref "R5") (pin "2") (pinfunction "2_2") (pintype "passive"))
    )
    (net (code "78") (name "Net-(LED6-PadC)") (class "Default")
      (node (ref "LED6") (pin "C") (pinfunction "C_C") (pintype "passive"))
      (node (ref "R6") (pin "2") (pinfunction "2_2") (pintype "passive"))
    )
    (net (code "79") (name "Net-(LED7-PadC)") (class "Default")
      (node (ref "LED7") (pin "C") (pinfunction "C_C") (pintype "passive"))
      (node (ref "R7") (pin "2") (pinfunction "2_2") (pintype "passive"))
    )
    (net (code "80") (name "Net-(LED8-PadC)") (class "Default")
      (node (ref "LED8") (pin "C") (pinfunction "C_C") (pintype "passive"))
      (node (ref "R24") (pin "2") (pinfunction "2_2") (pintype "passive"))
    )
    (net (code "81") (name "Net-(LED9-PadC)") (class "Default")
      (node (ref "LED9") (pin "C") (pinfunction "C_C") (pintype "passive"))
      (node (ref "R25") (pin "2") (pinfunction "2_2") (pintype "passive"))
    )
    (net (code "82") (name "Net-(LINEAR_ACTUATOR_1A-KL)") (class "Default")
      (node (ref "LINEAR_ACTUATOR_1") (pin "1") (pinfunction "KL_1") (pintype "passive"))
      (node (ref "R10") (pin "2") (pinfunction "2_2") (pintype "passive"))
    )
    (net (code "83") (name "Net-(LINEAR_ACTUATOR_1B-KL)") (class "Default")
      (node (ref "LINEAR_ACTUATOR_1") (pin "2") (pinfunction "KL_2") (pintype "passive"))
      (node (ref "R11") (pin "2") (pinfunction "2_2") (pintype "passive"))
    )
    (net (code "84") (name "Net-(LINEAR_ACTUATOR_2A-KL)") (class "Default")
      (node (ref "LINEAR_ACTUATOR_2") (pin "1") (pinfunction "KL_1") (pintype "passive"))
      (node (ref "R12") (pin "2") (pinfunction "2_2") (pintype "passive"))
    )
    (net (code "85") (name "Net-(LINEAR_ACTUATOR_2B-KL)") (class "Default")
      (node (ref "LINEAR_ACTUATOR_2") (pin "2") (pinfunction "KL_2") (pintype "passive"))
      (node (ref "R13") (pin "2") (pinfunction "2_2") (pintype "passive"))
    )
    (net (code "86") (name "Net-(LINEAR_ACTUATOR_3A-KL)") (class "Default")
      (node (ref "LINEAR_ACTUATOR_3") (pin "1") (pinfunction "KL_1") (pintype "passive"))
      (node (ref "R14") (pin "2") (pinfunction "2_2") (pintype "passive"))
    )
    (net (code "87") (name "Net-(LINEAR_ACTUATOR_3B-KL)") (class "Default")
      (node (ref "LINEAR_ACTUATOR_3") (pin "2") (pinfunction "KL_2") (pintype "passive"))
      (node (ref "R15") (pin "2") (pinfunction "2_2") (pintype "passive"))
    )
    (net (code "88") (name "Net-(ODROIDA-KL)") (class "Default")
      (node (ref "ODROID") (pin "1") (pinfunction "KL_1") (pintype "passive"))
      (node (ref "OK1") (pin "1") (pinfunction "A_1") (pintype "passive"))
    )
    (net (code "89") (name "Net-(OK1-C)") (class "Default")
      (node (ref "OK1") (pin "2") (pinfunction "C_2") (pintype "passive"))
      (node (ref "R22") (pin "2") (pinfunction "2_2") (pintype "passive"))
    )
    (net (code "90") (name "Net-(S1-COM)") (class "Default")
      (node (ref "R30") (pin "2") (pinfunction "2_2") (pintype "passive"))
      (node (ref "S1") (pin "1") (pinfunction "COM_1") (pintype "bidirectional"))
    )
    (net (code "91") (name "PW1") (class "Default")
      (node (ref "D7") (pin "2") (pinfunction "A2_2") (pintype "passive"))
      (node (ref "U$1") (pin "7") (pinfunction "7_7") (pintype "bidirectional"))
    )
    (net (code "92") (name "PWM3") (class "Default")
      (node (ref "D9") (pin "2") (pinfunction "A2_2") (pintype "passive"))
      (node (ref "U$1") (pin "5") (pinfunction "5_5") (pintype "bidirectional"))
    )
    (net (code "93") (name "PWM4") (class "Default")
      (node (ref "D10") (pin "2") (pinfunction "A2_2") (pintype "passive"))
      (node (ref "U$1") (pin "4") (pinfunction "4_4") (pintype "bidirectional"))
    )
    (net (code "94") (name "PWM5") (class "Default")
      (node (ref "D11") (pin "2") (pinfunction "A2_2") (pintype "passive"))
      (node (ref "U$1") (pin "3") (pinfunction "3_3") (pintype "bidirectional"))
    )
    (net (code "95") (name "PWM6") (class "Default")
      (node (ref "D12") (pin "2") (pinfunction "A2_2") (pintype "passive"))
      (node (ref "U$1") (pin "2") (pinfunction "2_2") (pintype "bidirectional"))
    )
    (net (code "96") (name "PWN2") (class "Default")
      (node (ref "D8") (pin "2") (pinfunction "A2_2") (pintype "passive"))
      (node (ref "U$1") (pin "6") (pinfunction "6_6") (pintype "bidirectional"))
    )
    (net (code "97") (name "RC") (class "Default")
      (node (ref "IC1") (pin "2") (pinfunction "I1_2") (pintype "input"))
      (node (ref "IC1") (pin "5") (pinfunction "I1_5") (pintype "input"))
      (node (ref "IC2") (pin "2") (pinfunction "I1_2") (pintype "input"))
      (node (ref "IC2") (pin "5") (pinfunction "I1_5") (pintype "input"))
      (node (ref "IC5") (pin "1") (pinfunction "1OUT_1") (pintype "bidirectional"))
      (node (ref "R31") (pin "2") (pinfunction "2_2") (pintype "passive"))
    )
    (net (code "98") (name "TX1") (class "Default")
      (node (ref "SABERTOOTH") (pin "1") (pinfunction "KL_1") (pintype "passive"))
      (node (ref "U$1") (pin "18") (pinfunction "18_18") (pintype "bidirectional"))
    )
    (net (code "99") (name "VCC") (class "Default")
      (node (ref "IC11") (pin "1") (pinfunction "CLR_1") (pintype "input"))
      (node (ref "IC11") (pin "10") (pinfunction "PRE_10") (pintype "input"))
      (node (ref "IC11") (pin "13") (pinfunction "CLR_13") (pintype "input"))
      (node (ref "IC11") (pin "4") (pinfunction "PRE_4") (pintype "input"))
      (node (ref "IC5") (pin "8") (pinfunction "VCC_8") (pintype "bidirectional"))
      (node (ref "IC6") (pin "4") (pinfunction "R_4") (pintype "input"))
      (node (ref "IC6") (pin "8") (pinfunction "V+_8") (pintype "power_in"))
      (node (ref "JP1") (pin "1") (pinfunction "1_1") (pintype "passive"))
      (node (ref "JP2") (pin "1") (pinfunction "1_1") (pintype "passive"))
      (node (ref "JP3") (pin "1") (pinfunction "1_1") (pintype "passive"))
      (node (ref "JP4") (pin "1") (pinfunction "1_1") (pintype "passive"))
      (node (ref "JP5") (pin "1") (pinfunction "1_1") (pintype "passive"))
      (node (ref "JP6") (pin "1") (pinfunction "1_1") (pintype "passive"))
      (node (ref "R23") (pin "2") (pinfunction "2_2") (pintype "passive"))
      (node (ref "R26") (pin "2") (pinfunction "2_2") (pintype "passive"))
      (node (ref "R28") (pin "2") (pinfunction "2_2") (pintype "passive"))
      (node (ref "R31") (pin "1") (pinfunction "1_1") (pintype "passive"))
      (node (ref "R8") (pin "2") (pinfunction "2_2") (pintype "passive"))
      (node (ref "U$1") (pin "5V") (pinfunction "5V_5V") (pintype "bidirectional"))
    )
    (net (code "100") (name "unconnected-(IC5-2IN+-Pad5)") (class "Default")
      (node (ref "IC5") (pin "5") (pinfunction "2IN+_5") (pintype "bidirectional"))
    )
    (net (code "101") (name "unconnected-(IC5-2IN--Pad6)") (class "Default")
      (node (ref "IC5") (pin "6") (pinfunction "2IN-_6") (pintype "bidirectional"))
    )
    (net (code "102") (name "unconnected-(IC5-2OUT-Pad7)") (class "Default")
      (node (ref "IC5") (pin "7") (pinfunction "2OUT_7") (pintype "bidirectional"))
    )
    (net (code "103") (name "unconnected-(U$1-GND-PadGND@2)") (class "Default")
      (node (ref "U$1") (pin "GND@2") (pinfunction "GND_GND@2") (pintype "bidirectional"))
    )
    (net (code "104") (name "unconnected-(U$1-GND-PadGND@3)") (class "Default")
      (node (ref "U$1") (pin "GND@3") (pinfunction "GND_GND@3") (pintype "bidirectional"))
    )
    (net (code "105") (name "unconnected-(U$1-Pad0)") (class "Default")
      (node (ref "U$1") (pin "0") (pinfunction "0_0") (pintype "bidirectional"))
    )
    (net (code "106") (name "unconnected-(U$1-Pad1)") (class "Default")
      (node (ref "U$1") (pin "1") (pinfunction "1_1") (pintype "bidirectional"))
    )
    (net (code "107") (name "unconnected-(U$1-Pad3V3)") (class "Default")
      (node (ref "U$1") (pin "3V3") (pinfunction "3V3_3V3") (pintype "bidirectional"))
    )
    (net (code "108") (name "unconnected-(U$1-Pad11)") (class "Default")
      (node (ref "U$1") (pin "11") (pinfunction "11_11") (pintype "bidirectional"))
    )
    (net (code "109") (name "unconnected-(U$1-Pad12)") (class "Default")
      (node (ref "U$1") (pin "12") (pinfunction "12_12") (pintype "bidirectional"))
    )
    (net (code "110") (name "unconnected-(U$1-Pad13)") (class "Default")
      (node (ref "U$1") (pin "13") (pinfunction "13_13") (pintype "bidirectional"))
    )
    (net (code "111") (name "unconnected-(U$1-Pad14)") (class "Default")
      (node (ref "U$1") (pin "14") (pinfunction "14_14") (pintype "bidirectional"))
    )
    (net (code "112") (name "unconnected-(U$1-Pad15)") (class "Default")
      (node (ref "U$1") (pin "15") (pinfunction "15_15") (pintype "bidirectional"))
    )
    (net (code "113") (name "unconnected-(U$1-Pad16)") (class "Default")
      (node (ref "U$1") (pin "16") (pinfunction "16_16") (pintype "bidirectional"))
    )
    (net (code "114") (name "unconnected-(U$1-Pad17)") (class "Default")
      (node (ref "U$1") (pin "17") (pinfunction "17_17") (pintype "bidirectional"))
    )
    (net (code "115") (name "unconnected-(U$1-Pad19)") (class "Default")
      (node (ref "U$1") (pin "19") (pinfunction "19_19") (pintype "bidirectional"))
    )
    (net (code "116") (name "unconnected-(U$1-Pad20)") (class "Default")
      (node (ref "U$1") (pin "20") (pinfunction "20_20") (pintype "bidirectional"))
    )
    (net (code "117") (name "unconnected-(U$1-Pad21)") (class "Default")
      (node (ref "U$1") (pin "21") (pinfunction "21_21") (pintype "bidirectional"))
    )
    (net (code "118") (name "unconnected-(U$1-Pad32)") (class "Default")
      (node (ref "U$1") (pin "32") (pinfunction "32_32") (pintype "bidirectional"))
    )
    (net (code "119") (name "unconnected-(U$1-Pad33)") (class "Default")
      (node (ref "U$1") (pin "33") (pinfunction "33_33") (pintype "bidirectional"))
    )
    (net (code "120") (name "unconnected-(U$1-Pad34)") (class "Default")
      (node (ref "U$1") (pin "34") (pinfunction "34_34") (pintype "bidirectional"))
    )
    (net (code "121") (name "unconnected-(U$1-Pad35)") (class "Default")
      (node (ref "U$1") (pin "35") (pinfunction "35_35") (pintype "bidirectional"))
    )
    (net (code "122") (name "unconnected-(U$1-Pad36)") (class "Default")
      (node (ref "U$1") (pin "36") (pinfunction "36_36") (pintype "bidirectional"))
    )
    (net (code "123") (name "unconnected-(U$1-Pad37)") (class "Default")
      (node (ref "U$1") (pin "37") (pinfunction "37_37") (pintype "bidirectional"))
    )
    (net (code "124") (name "unconnected-(U$1-Pad38)") (class "Default")
      (node (ref "U$1") (pin "38") (pinfunction "38_38") (pintype "bidirectional"))
    )
    (net (code "125") (name "unconnected-(U$1-Pad39)") (class "Default")
      (node (ref "U$1") (pin "39") (pinfunction "39_39") (pintype "bidirectional"))
    )
    (net (code "126") (name "unconnected-(U$1-Pad40)") (class "Default")
      (node (ref "U$1") (pin "40") (pinfunction "40_40") (pintype "bidirectional"))
    )
    (net (code "127") (name "unconnected-(U$1-Pad42)") (class "Default")
      (node (ref "U$1") (pin "42") (pinfunction "42_42") (pintype "bidirectional"))
    )
    (net (code "128") (name "unconnected-(U$1-Pad44)") (class "Default")
      (node (ref "U$1") (pin "44") (pinfunction "44_44") (pintype "bidirectional"))
    )
    (net (code "129") (name "unconnected-(U$1-Pad46)") (class "Default")
      (node (ref "U$1") (pin "46") (pinfunction "46_46") (pintype "bidirectional"))
    )
    (net (code "130") (name "unconnected-(U$1-Pad48)") (class "Default")
      (node (ref "U$1") (pin "48") (pinfunction "48_48") (pintype "bidirectional"))
    )
    (net (code "131") (name "unconnected-(U$1-Pad50)") (class "Default")
      (node (ref "U$1") (pin "50") (pinfunction "50_50") (pintype "bidirectional"))
    )
    (net (code "132") (name "unconnected-(U$1-PadA2)") (class "Default")
      (node (ref "U$1") (pin "A2") (pinfunction "A2_A2") (pintype "bidirectional"))
    )
    (net (code "133") (name "unconnected-(U$1-PadA3)") (class "Default")
      (node (ref "U$1") (pin "A3") (pinfunction "A3_A3") (pintype "bidirectional"))
    )
    (net (code "134") (name "unconnected-(U$1-PadA4)") (class "Default")
      (node (ref "U$1") (pin "A4") (pinfunction "A4_A4") (pintype "bidirectional"))
    )
    (net (code "135") (name "unconnected-(U$1-PadA5)") (class "Default")
      (node (ref "U$1") (pin "A5") (pinfunction "A5_A5") (pintype "bidirectional"))
    )
    (net (code "136") (name "unconnected-(U$1-PadA6)") (class "Default")
      (node (ref "U$1") (pin "A6") (pinfunction "A6_A6") (pintype "bidirectional"))
    )
    (net (code "137") (name "unconnected-(U$1-PadA7)") (class "Default")
      (node (ref "U$1") (pin "A7") (pinfunction "A7_A7") (pintype "bidirectional"))
    )
    (net (code "138") (name "unconnected-(U$1-PadA8)") (class "Default")
      (node (ref "U$1") (pin "A8") (pinfunction "A8_A8") (pintype "bidirectional"))
    )
    (net (code "139") (name "unconnected-(U$1-PadA9)") (class "Default")
      (node (ref "U$1") (pin "A9") (pinfunction "A9_A9") (pintype "bidirectional"))
    )
    (net (code "140") (name "unconnected-(U$1-PadA10)") (class "Default")
      (node (ref "U$1") (pin "A10") (pinfunction "A10_A10") (pintype "bidirectional"))
    )
    (net (code "141") (name "unconnected-(U$1-PadA11)") (class "Default")
      (node (ref "U$1") (pin "A11") (pinfunction "A11_A11") (pintype "bidirectional"))
    )
    (net (code "142") (name "unconnected-(U$1-PadA12)") (class "Default")
      (node (ref "U$1") (pin "A12") (pinfunction "A12_A12") (pintype "bidirectional"))
    )
    (net (code "143") (name "unconnected-(U$1-PadA13)") (class "Default")
      (node (ref "U$1") (pin "A13") (pinfunction "A13_A13") (pintype "bidirectional"))
    )
    (net (code "144") (name "unconnected-(U$1-PadA14)") (class "Default")
      (node (ref "U$1") (pin "A14") (pinfunction "A14_A14") (pintype "bidirectional"))
    )
    (net (code "145") (name "unconnected-(U$1-PadA15)") (class "Default")
      (node (ref "U$1") (pin "A15") (pinfunction "A15_A15") (pintype "bidirectional"))
    )
    (net (code "146") (name "unconnected-(U$1-PadAREF)") (class "Default")
      (node (ref "U$1") (pin "AREF") (pinfunction "AREF_AREF") (pintype "bidirectional"))
    )
    (net (code "147") (name "unconnected-(U$1-PadRESET)") (class "Default")
      (node (ref "U$1") (pin "RESET") (pinfunction "RESET_RESET") (pintype "bidirectional"))
    )
    (net (code "148") (name "unconnected-(U$1-PadVIN)") (class "Default")
      (node (ref "U$1") (pin "VIN") (pinfunction "VIN_VIN") (pintype "bidirectional"))
    )
  )
)
